# Power.net
KiCad netlist of a schematic drawn in Altium Designer
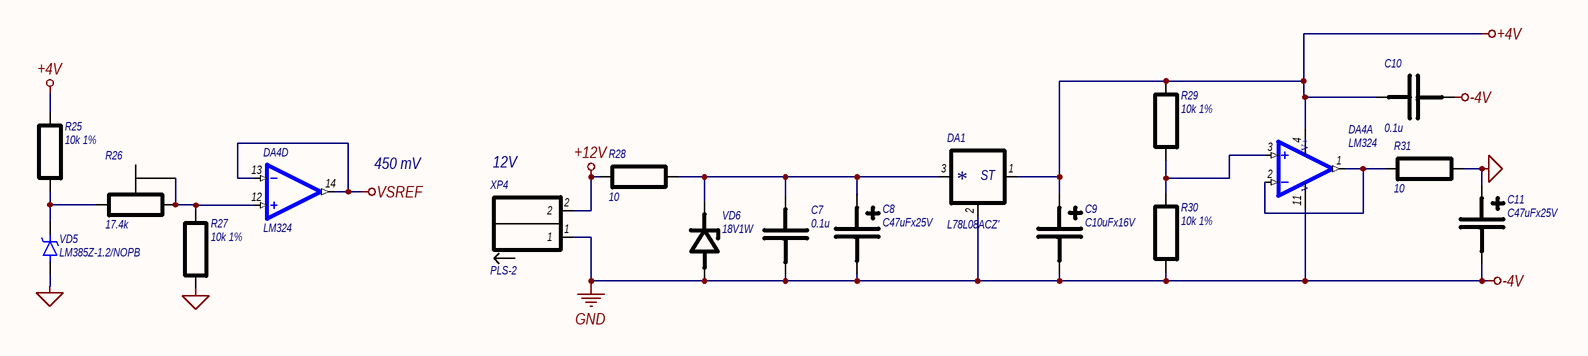
[diagram p0: Power.SchDoc]

(export (version "E")
  (design (tool "Eeschema 10.0.6"))
  (components
    (comp (ref "C7")
      (value "0.1u")
      (footprint "CR2012-0805")
      (libsource (lib "sobol_lib") (part "C0805-0.1u-X7R"))
    )
    (comp (ref "C8")
      (value "C47uFx25V")
      (footprint "C6.3x11")
      (libsource (lib "sobol_lib") (part "C47uFx25V"))
    )
    (comp (ref "C9")
      (value "C10uFx16V")
      (footprint "C6.3x11")
      (libsource (lib "sobol_lib") (part "C10uFx16V"))
    )
    (comp (ref "C10")
      (value "0.1u")
      (footprint "CR2012-0805")
      (libsource (lib "sobol_lib") (part "C0805-0.1u-X7R"))
    )
    (comp (ref "C11")
      (value "C47uFx25V")
      (footprint "C6.3x11")
      (libsource (lib "sobol_lib") (part "C47uFx25V"))
    )
    (comp (ref "DA1")
      (value "L78L08ACZ'")
      (footprint "to-92")
      (libsource (lib "sobol_lib") (part "L78L08ACZ'"))
    )
    (comp (ref "DA4")
      (value "LM324")
      (footprint "SOIC127P600X175-14N")
      (description "General Purpose Amplifier 4 Circuit 14-SOIC")
      (fields (field (name "MF") "Texas Instruments"))
      (libsource (lib "sobol_lib") (part "LM324"))
    )
    (comp (ref "R25")
      (value "10k 1%")
      (footprint "CR2012-0805")
      (libsource (lib "sobol_lib") (part "R0805-10k-1%"))
    )
    (comp (ref "R26") (value "17.4k") (footprint "3296W") (libsource (lib "sobol_lib") (part "3296W-1-103")))
    (comp (ref "R27")
      (value "10k 1%")
      (footprint "CR2012-0805")
      (libsource (lib "sobol_lib") (part "R0805-10k-1%"))
    )
    (comp (ref "R28") (value "10") (footprint "R-1W") (libsource (lib "sobol_lib") (part "R-1W-10R")))
    (comp (ref "R29")
      (value "10k 1%")
      (footprint "CR2012-0805")
      (libsource (lib "sobol_lib") (part "R0805-10k-1%"))
    )
    (comp (ref "R30")
      (value "10k 1%")
      (footprint "CR2012-0805")
      (libsource (lib "sobol_lib") (part "R0805-10k-1%"))
    )
    (comp (ref "R31") (value "10") (footprint "R-1W") (libsource (lib "sobol_lib") (part "R-1W-10R")))
    (comp (ref "VD5")
      (value "LM385Z-1.2/NOPB")
      (footprint "DIO_LM385Z-2.5/NOPB")
      (description "Shunt Voltage Reference IC Â±3% TO-92-3")
      (fields (field (name "MF") "ON Semiconductor") (field (name "MP") "LM385Z-2.5"))
      (libsource (lib "sobol_lib") (part "LM385Z-2.5/NOPB"))
    )
    (comp (ref "VD6") (value "18V1W") (footprint "DO-41") (libsource (lib "sobol_lib") (part "1N4746A")))
    (comp (ref "XP4") (value "PLS-2") (footprint "PLS-2") (libsource (lib "sobol_lib") (part "PLS-2")))
  )
  (nets
    (net (code "1") (name "+4V") (class "Default")
      (node (ref "C10") (pin "1") (pinfunction "1_1") (pintype "passive"))
      (node (ref "C9") (pin "1") (pinfunction "1_1") (pintype "passive"))
      (node (ref "DA1") (pin "1") (pinfunction "Vout_1") (pintype "passive"))
      (node (ref "DA4") (pin "4") (pinfunction "VCC+_4") (pintype "power_in"))
      (node (ref "R25") (pin "2") (pinfunction "2_2") (pintype "passive"))
      (node (ref "R29") (pin "2") (pinfunction "2_2") (pintype "passive"))
    )
    (net (code "2") (name "+12V") (class "Default")
      (node (ref "R28") (pin "1") (pinfunction "1_1") (pintype "passive"))
      (node (ref "XP4") (pin "2") (pinfunction "2_2") (pintype "passive"))
    )
    (net (code "3") (name "-4V") (class "Default")
      (node (ref "C10") (pin "2") (pinfunction "2_2") (pintype "passive"))
      (node (ref "C11") (pin "2") (pinfunction "2_2") (pintype "passive"))
      (node (ref "C7") (pin "2") (pinfunction "2_2") (pintype "passive"))
      (node (ref "C8") (pin "2") (pinfunction "2_2") (pintype "passive"))
      (node (ref "C9") (pin "2") (pinfunction "2_2") (pintype "passive"))
      (node (ref "DA1") (pin "2") (pinfunction "GND_2") (pintype "passive"))
      (node (ref "DA4") (pin "11") (pinfunction "VCC-_11") (pintype "power_in"))
      (node (ref "R30") (pin "1") (pinfunction "1_1") (pintype "passive"))
      (node (ref "VD6") (pin "1") (pinfunction "A_1") (pintype "passive"))
      (node (ref "XP4") (pin "1") (pinfunction "1_1") (pintype "passive"))
    )
    (net (code "4") (name "Net-(DA1-Vin)") (class "Default")
      (node (ref "C7") (pin "1") (pinfunction "1_1") (pintype "passive"))
      (node (ref "C8") (pin "1") (pinfunction "1_1") (pintype "passive"))
      (node (ref "DA1") (pin "3") (pinfunction "Vin_3") (pintype "passive"))
      (node (ref "R28") (pin "2") (pinfunction "2_2") (pintype "passive"))
      (node (ref "VD6") (pin "2") (pinfunction "K_2") (pintype "passive"))
    )
    (net (code "5") (name "Net-(DA4A-INVERTING_INPUT1)") (class "Default")
      (node (ref "DA4") (pin "1") (pinfunction "OUTPUT1_1") (pintype "output"))
      (node (ref "DA4") (pin "2") (pinfunction "INVERTING_INPUT1_2") (pintype "input"))
      (node (ref "R31") (pin "1") (pinfunction "1_1") (pintype "passive"))
    )
    (net (code "6") (name "Net-(DA4A-NON-INVERTING_INPUT1)") (class "Default")
      (node (ref "DA4") (pin "3") (pinfunction "NON-INVERTING_INPUT1_3") (pintype "input"))
      (node (ref "R29") (pin "1") (pinfunction "1_1") (pintype "passive"))
      (node (ref "R30") (pin "2") (pinfunction "2_2") (pintype "passive"))
    )
    (net (code "7") (name "Net-(DA4D-NON-INVERTING_INPUT4)") (class "Default")
      (node (ref "DA4") (pin "12") (pinfunction "NON-INVERTING_INPUT4_12") (pintype "input"))
      (node (ref "R26") (pin "2") (pinfunction "2_2") (pintype "passive"))
      (node (ref "R26") (pin "3") (pinfunction "3_3") (pintype "passive"))
      (node (ref "R27") (pin "2") (pinfunction "2_2") (pintype "passive"))
    )
    (net (code "8") (name "Net-(VD5-C)") (class "Default")
      (node (ref "R25") (pin "1") (pinfunction "1_1") (pintype "passive"))
      (node (ref "R26") (pin "1") (pinfunction "1_1") (pintype "passive"))
      (node (ref "VD5") (pin "2") (pinfunction "C_2") (pintype "passive"))
    )
    (net (code "9") (name "SGND") (class "Default")
      (node (ref "C11") (pin "1") (pinfunction "1_1") (pintype "passive"))
      (node (ref "R27") (pin "1") (pinfunction "1_1") (pintype "passive"))
      (node (ref "R31") (pin "2") (pinfunction "2_2") (pintype "passive"))
      (node (ref "VD5") (pin "1") (pinfunction "A_1") (pintype "passive"))
    )
    (net (code "10") (name "VSREF") (class "Default")
      (node (ref "DA4") (pin "13") (pinfunction "INVERTING_INPUT4_13") (pintype "input"))
      (node (ref "DA4") (pin "14") (pinfunction "OUTPUT4_14") (pintype "output"))
    )
  )
)
